# oTFTeatherWing-LT7688.net
KiCad netlist of a schematic drawn in EAGLE
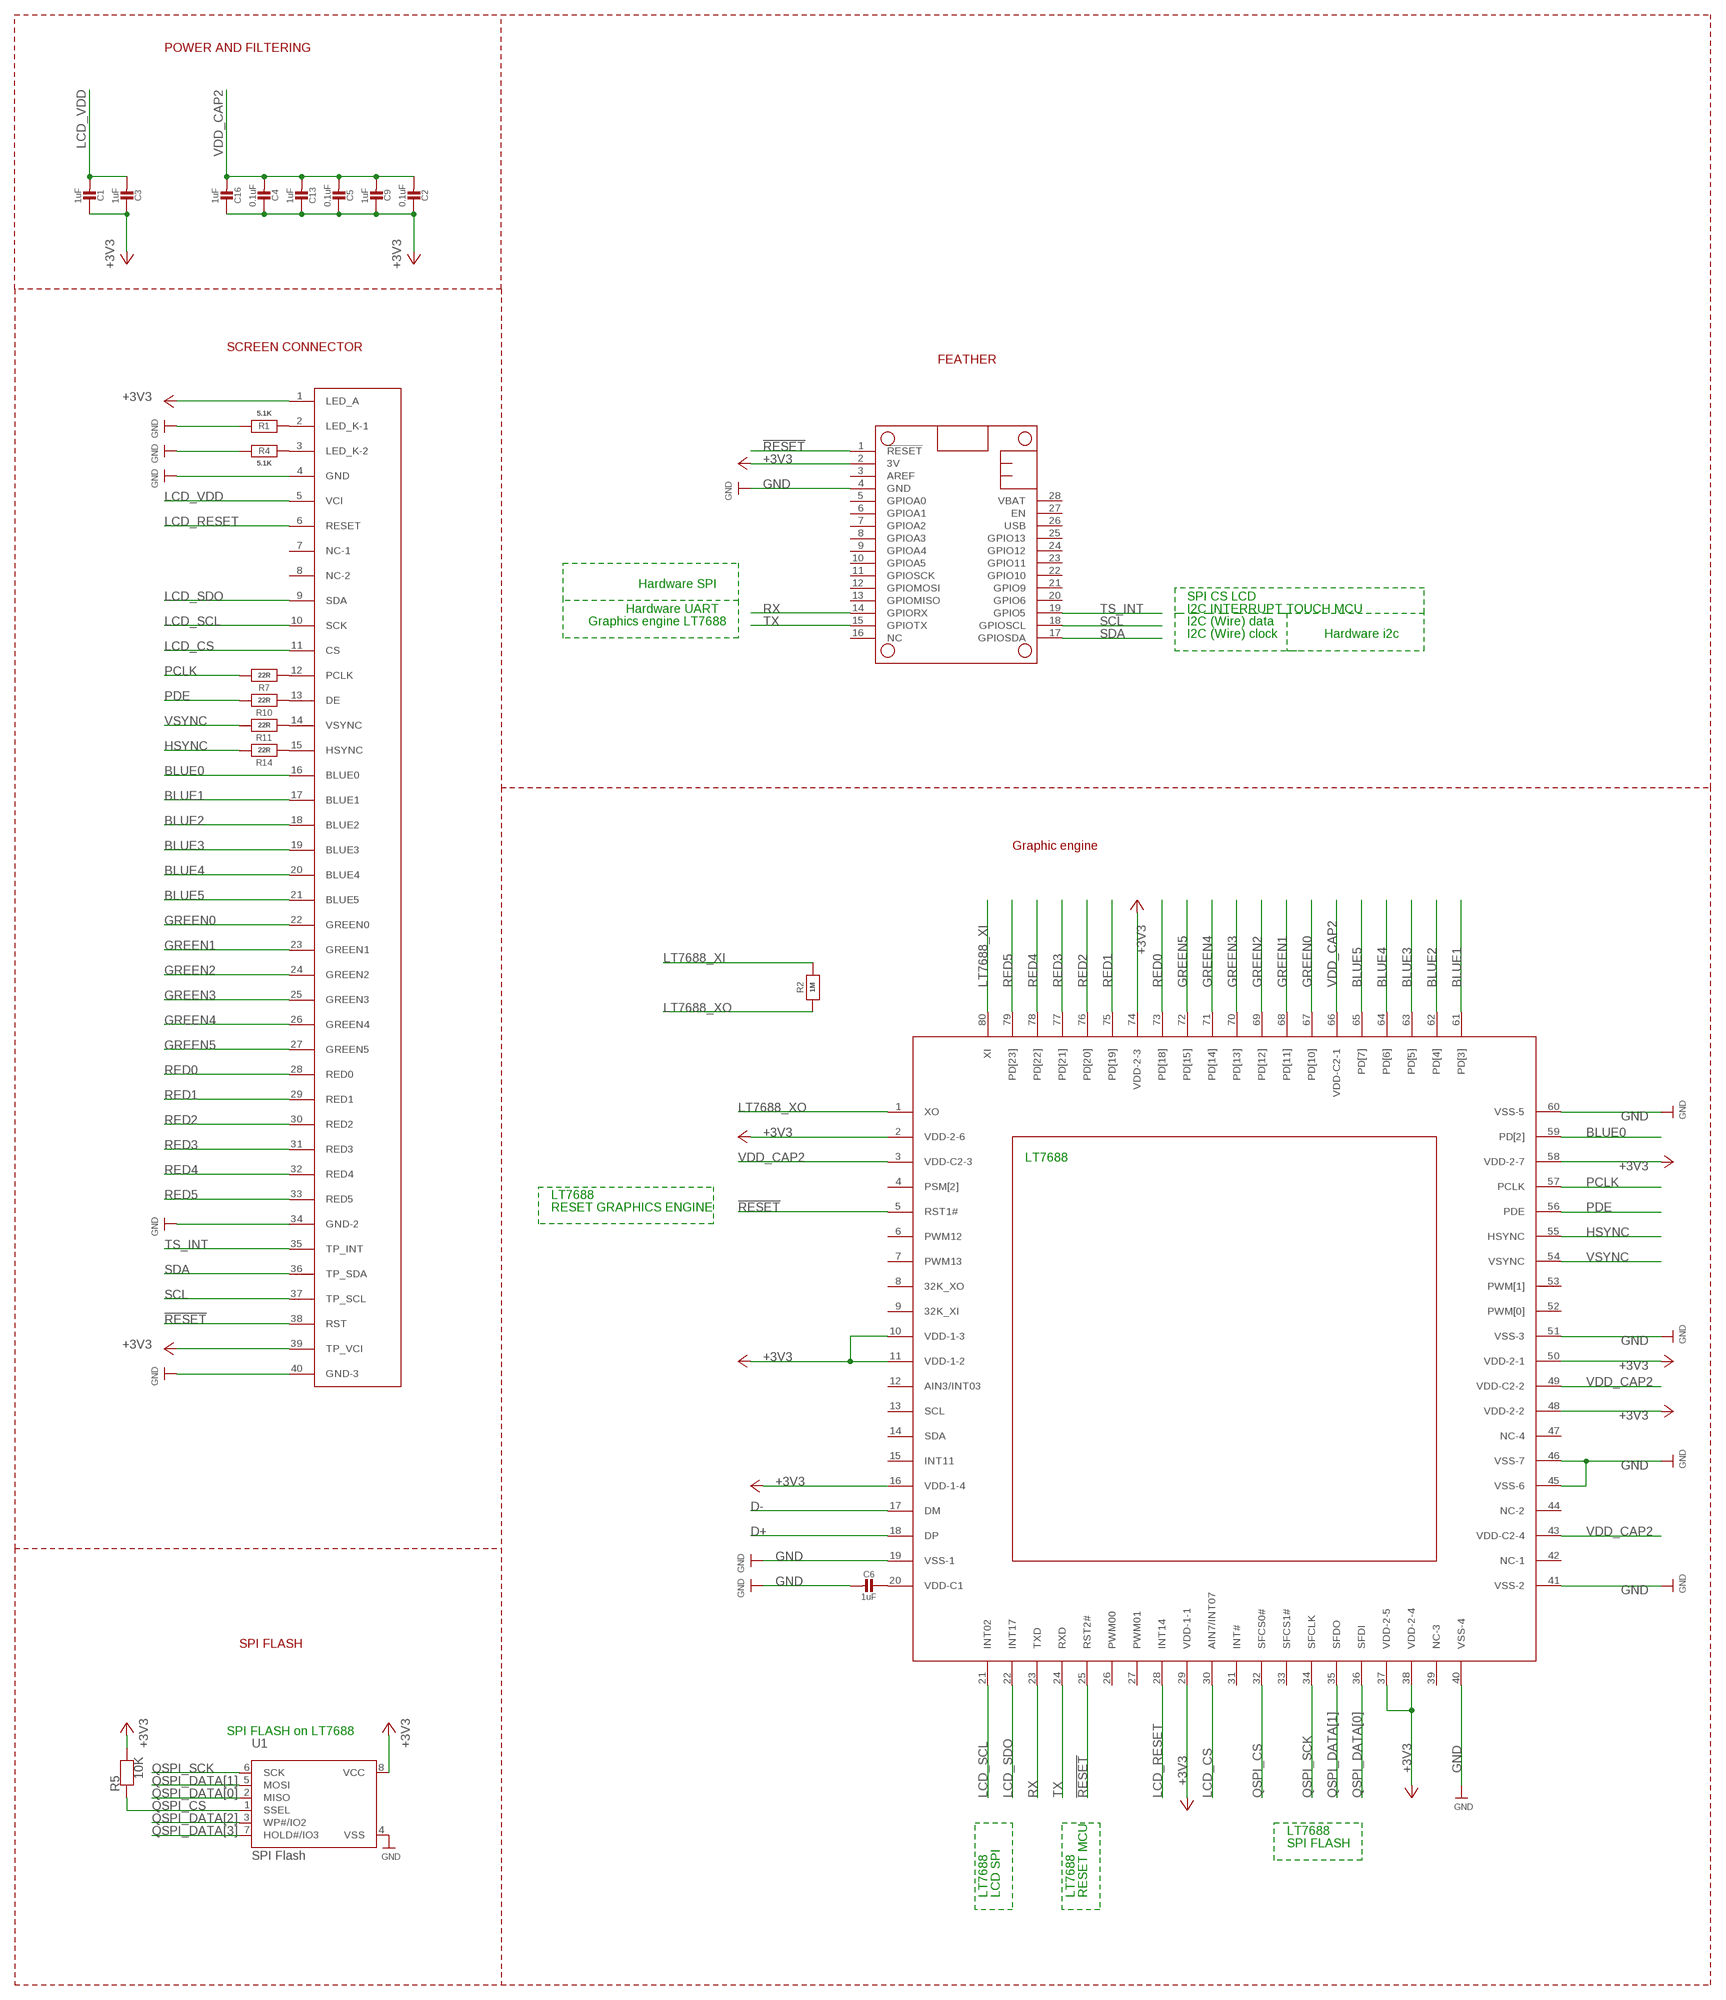
[diagram p0: schematic, sheet 1]

(export (version "E")
  (design (tool "Eeschema 10.0.6"))
  (components
    (comp (ref "C1")
      (value "1uF")
      (footprint "eagle-import:0603-NO")
      (libsource (lib "eagle-import") (part "CAP_CERAMIC0603_NO"))
    )
    (comp (ref "C2")
      (value "0.1uF")
      (footprint "eagle-import:0603-NO")
      (libsource (lib "eagle-import") (part "CAP_CERAMIC0603_NO"))
    )
    (comp (ref "C3")
      (value "1uF")
      (footprint "eagle-import:0603-NO")
      (libsource (lib "eagle-import") (part "CAP_CERAMIC0603_NO"))
    )
    (comp (ref "C4")
      (value "0.1uF")
      (footprint "eagle-import:0603-NO")
      (libsource (lib "eagle-import") (part "CAP_CERAMIC0603_NO"))
    )
    (comp (ref "C5")
      (value "0.1uF")
      (footprint "eagle-import:0603-NO")
      (libsource (lib "eagle-import") (part "CAP_CERAMIC0603_NO"))
    )
    (comp (ref "C6")
      (value "1uF")
      (footprint "eagle-import:0603-NO")
      (libsource (lib "eagle-import") (part "CAP_CERAMIC0603_NO"))
    )
    (comp (ref "C9")
      (value "1uF")
      (footprint "eagle-import:0603-NO")
      (libsource (lib "eagle-import") (part "CAP_CERAMIC0603_NO"))
    )
    (comp (ref "C13")
      (value "1uF")
      (footprint "eagle-import:0603-NO")
      (libsource (lib "eagle-import") (part "CAP_CERAMIC0603_NO"))
    )
    (comp (ref "C16")
      (value "1uF")
      (footprint "eagle-import:0603-NO")
      (libsource (lib "eagle-import") (part "CAP_CERAMIC0603_NO"))
    )
    (comp (ref "MS2")
      (value "FEATHERWING")
      (footprint "eagle-import:FEATHERWING")
      (libsource (lib "eagle-import") (part "FEATHERWING"))
    )
    (comp (ref "R1")
      (value "5.1K")
      (footprint "eagle-import:0603-NO")
      (libsource (lib "eagle-import") (part "RESISTOR_0603_NOOUT"))
    )
    (comp (ref "R2")
      (value "1M")
      (footprint "eagle-import:0603-NO")
      (libsource (lib "eagle-import") (part "RESISTOR_0603_NOOUT"))
    )
    (comp (ref "R4")
      (value "5.1K")
      (footprint "eagle-import:0603-NO")
      (libsource (lib "eagle-import") (part "RESISTOR_0603_NOOUT"))
    )
    (comp (ref "R5")
      (value "10K")
      (footprint "eagle-import:0603-NO")
      (libsource (lib "eagle-import") (part "RESISTOR_0603_NOOUT"))
    )
    (comp (ref "R7")
      (value "22R")
      (footprint "eagle-import:0603-NO")
      (libsource (lib "eagle-import") (part "RESISTOR_0603_NOOUT"))
    )
    (comp (ref "R10")
      (value "22R")
      (footprint "eagle-import:0603-NO")
      (libsource (lib "eagle-import") (part "RESISTOR_0603_NOOUT"))
    )
    (comp (ref "R11")
      (value "22R")
      (footprint "eagle-import:0603-NO")
      (libsource (lib "eagle-import") (part "RESISTOR_0603_NOOUT"))
    )
    (comp (ref "R14")
      (value "22R")
      (footprint "eagle-import:0603-NO")
      (libsource (lib "eagle-import") (part "RESISTOR_0603_NOOUT"))
    )
    (comp (ref "U$1")
      (value "LT7688")
      (footprint "eagle-import:QFN40P900X900X70-81T710N")
      (libsource (lib "eagle-import") (part "LT7688"))
    )
    (comp (ref "U$2")
      (value "FPC-LCD")
      (footprint "eagle-import:XF2M-4015-1F-REVERSE")
      (libsource (lib "eagle-import") (part "FPC-LCD"))
    )
    (comp (ref "U1")
      (value "SPI Flash")
      (footprint "eagle-import:USON8")
      (libsource (lib "eagle-import") (part "SPIFLASH_8PINUX"))
    )
  )
  (nets
    (net (code "1") (name "+3V3") (class "Default")
      (node (ref "C1") (pin "1") (pinfunction "1_1") (pintype "passive"))
      (node (ref "C13") (pin "1") (pinfunction "1_1") (pintype "passive"))
      (node (ref "C16") (pin "1") (pinfunction "1_1") (pintype "passive"))
      (node (ref "C2") (pin "1") (pinfunction "1_1") (pintype "passive"))
      (node (ref "C3") (pin "1") (pinfunction "1_1") (pintype "passive"))
      (node (ref "C4") (pin "1") (pinfunction "1_1") (pintype "passive"))
      (node (ref "C5") (pin "1") (pinfunction "1_1") (pintype "passive"))
      (node (ref "C9") (pin "1") (pinfunction "1_1") (pintype "passive"))
      (node (ref "MS2") (pin "2") (pinfunction "3V_2") (pintype "power_in"))
      (node (ref "R5") (pin "2") (pinfunction "2_2") (pintype "passive"))
      (node (ref "U$1") (pin "10") (pinfunction "VDD-1-3_10") (pintype "bidirectional"))
      (node (ref "U$1") (pin "11") (pinfunction "VDD-1-2_11") (pintype "bidirectional"))
      (node (ref "U$1") (pin "16") (pinfunction "VDD-1-4_16") (pintype "bidirectional"))
      (node (ref "U$1") (pin "2") (pinfunction "VDD-2-6_2") (pintype "bidirectional"))
      (node (ref "U$1") (pin "29") (pinfunction "VDD-1-1_29") (pintype "bidirectional"))
      (node (ref "U$1") (pin "37") (pinfunction "VDD-2-5_37") (pintype "bidirectional"))
      (node (ref "U$1") (pin "38") (pinfunction "VDD-2-4_38") (pintype "bidirectional"))
      (node (ref "U$1") (pin "48") (pinfunction "VDD-2-2_48") (pintype "bidirectional"))
      (node (ref "U$1") (pin "50") (pinfunction "VDD-2-1_50") (pintype "bidirectional"))
      (node (ref "U$1") (pin "58") (pinfunction "VDD-2-7_58") (pintype "bidirectional"))
      (node (ref "U$1") (pin "74") (pinfunction "VDD-2-3_74") (pintype "bidirectional"))
      (node (ref "U$2") (pin "1") (pinfunction "LED_A_1") (pintype "bidirectional"))
      (node (ref "U$2") (pin "39") (pinfunction "TP_VCI_39") (pintype "bidirectional"))
      (node (ref "U1") (pin "8") (pinfunction "VCC_8") (pintype "bidirectional"))
    )
    (net (code "2") (name "/BLUE0") (class "Default")
      (node (ref "U$1") (pin "59") (pinfunction "PD[2]_59") (pintype "bidirectional"))
      (node (ref "U$2") (pin "16") (pinfunction "BLUE0_16") (pintype "bidirectional"))
    )
    (net (code "3") (name "/BLUE1") (class "Default")
      (node (ref "U$1") (pin "61") (pinfunction "PD[3]_61") (pintype "bidirectional"))
      (node (ref "U$2") (pin "17") (pinfunction "BLUE1_17") (pintype "bidirectional"))
    )
    (net (code "4") (name "/BLUE2") (class "Default")
      (node (ref "U$1") (pin "62") (pinfunction "PD[4]_62") (pintype "bidirectional"))
      (node (ref "U$2") (pin "18") (pinfunction "BLUE2_18") (pintype "bidirectional"))
    )
    (net (code "5") (name "/BLUE3") (class "Default")
      (node (ref "U$1") (pin "63") (pinfunction "PD[5]_63") (pintype "bidirectional"))
      (node (ref "U$2") (pin "19") (pinfunction "BLUE3_19") (pintype "bidirectional"))
    )
    (net (code "6") (name "/BLUE4") (class "Default")
      (node (ref "U$1") (pin "64") (pinfunction "PD[6]_64") (pintype "bidirectional"))
      (node (ref "U$2") (pin "20") (pinfunction "BLUE4_20") (pintype "bidirectional"))
    )
    (net (code "7") (name "/BLUE5") (class "Default")
      (node (ref "U$1") (pin "65") (pinfunction "PD[7]_65") (pintype "bidirectional"))
      (node (ref "U$2") (pin "21") (pinfunction "BLUE5_21") (pintype "bidirectional"))
    )
    (net (code "8") (name "/D+") (class "Default")
      (node (ref "U$1") (pin "18") (pinfunction "DP_18") (pintype "bidirectional"))
    )
    (net (code "9") (name "/D-") (class "Default")
      (node (ref "U$1") (pin "17") (pinfunction "DM_17") (pintype "bidirectional"))
    )
    (net (code "10") (name "/GREEN0") (class "Default")
      (node (ref "U$1") (pin "67") (pinfunction "PD[10]_67") (pintype "bidirectional"))
      (node (ref "U$2") (pin "22") (pinfunction "GREEN0_22") (pintype "bidirectional"))
    )
    (net (code "11") (name "/GREEN1") (class "Default")
      (node (ref "U$1") (pin "68") (pinfunction "PD[11]_68") (pintype "bidirectional"))
      (node (ref "U$2") (pin "23") (pinfunction "GREEN1_23") (pintype "bidirectional"))
    )
    (net (code "12") (name "/GREEN2") (class "Default")
      (node (ref "U$1") (pin "69") (pinfunction "PD[12]_69") (pintype "bidirectional"))
      (node (ref "U$2") (pin "24") (pinfunction "GREEN2_24") (pintype "bidirectional"))
    )
    (net (code "13") (name "/GREEN3") (class "Default")
      (node (ref "U$1") (pin "70") (pinfunction "PD[13]_70") (pintype "bidirectional"))
      (node (ref "U$2") (pin "25") (pinfunction "GREEN3_25") (pintype "bidirectional"))
    )
    (net (code "14") (name "/GREEN4") (class "Default")
      (node (ref "U$1") (pin "71") (pinfunction "PD[14]_71") (pintype "bidirectional"))
      (node (ref "U$2") (pin "26") (pinfunction "GREEN4_26") (pintype "bidirectional"))
    )
    (net (code "15") (name "/GREEN5") (class "Default")
      (node (ref "U$1") (pin "72") (pinfunction "PD[15]_72") (pintype "bidirectional"))
      (node (ref "U$2") (pin "27") (pinfunction "GREEN5_27") (pintype "bidirectional"))
    )
    (net (code "16") (name "/HSYNC") (class "Default")
      (node (ref "R14") (pin "2") (pinfunction "2_2") (pintype "passive"))
      (node (ref "U$1") (pin "55") (pinfunction "HSYNC_55") (pintype "bidirectional"))
    )
    (net (code "17") (name "/LCD_CS") (class "Default")
      (node (ref "U$1") (pin "30") (pinfunction "AIN7/INT07_30") (pintype "bidirectional"))
      (node (ref "U$2") (pin "11") (pinfunction "CS_11") (pintype "bidirectional"))
    )
    (net (code "18") (name "/LCD_RESET") (class "Default")
      (node (ref "U$1") (pin "28") (pinfunction "INT14_28") (pintype "bidirectional"))
      (node (ref "U$2") (pin "6") (pinfunction "RESET_6") (pintype "bidirectional"))
    )
    (net (code "19") (name "/LCD_SCL") (class "Default")
      (node (ref "U$1") (pin "21") (pinfunction "INT02_21") (pintype "bidirectional"))
      (node (ref "U$2") (pin "10") (pinfunction "SCK_10") (pintype "bidirectional"))
    )
    (net (code "20") (name "/LCD_SDO") (class "Default")
      (node (ref "U$1") (pin "22") (pinfunction "INT17_22") (pintype "bidirectional"))
      (node (ref "U$2") (pin "9") (pinfunction "SDA_9") (pintype "bidirectional"))
    )
    (net (code "21") (name "/LCD_VDD") (class "Default")
      (node (ref "C1") (pin "2") (pinfunction "2_2") (pintype "passive"))
      (node (ref "C3") (pin "2") (pinfunction "2_2") (pintype "passive"))
      (node (ref "U$2") (pin "5") (pinfunction "VCI_5") (pintype "bidirectional"))
    )
    (net (code "22") (name "/LT7688_XI") (class "Default")
      (node (ref "R2") (pin "2") (pinfunction "2_2") (pintype "passive"))
      (node (ref "U$1") (pin "80") (pinfunction "XI_80") (pintype "bidirectional"))
    )
    (net (code "23") (name "/LT7688_XO") (class "Default")
      (node (ref "R2") (pin "1") (pinfunction "1_1") (pintype "passive"))
      (node (ref "U$1") (pin "1") (pinfunction "XO_1") (pintype "bidirectional"))
    )
    (net (code "24") (name "/PCLK") (class "Default")
      (node (ref "R7") (pin "2") (pinfunction "2_2") (pintype "passive"))
      (node (ref "U$1") (pin "57") (pinfunction "PCLK_57") (pintype "bidirectional"))
    )
    (net (code "25") (name "/PDE") (class "Default")
      (node (ref "R10") (pin "2") (pinfunction "2_2") (pintype "passive"))
      (node (ref "U$1") (pin "56") (pinfunction "PDE_56") (pintype "bidirectional"))
    )
    (net (code "26") (name "/QSPI_CS") (class "Default")
      (node (ref "R5") (pin "1") (pinfunction "1_1") (pintype "passive"))
      (node (ref "U$1") (pin "32") (pinfunction "SFCS0#_32") (pintype "bidirectional"))
      (node (ref "U1") (pin "1") (pinfunction "SSEL_1") (pintype "bidirectional"))
    )
    (net (code "27") (name "/QSPI_DATA[0]") (class "Default")
      (node (ref "U$1") (pin "36") (pinfunction "SFDI_36") (pintype "bidirectional"))
      (node (ref "U1") (pin "2") (pinfunction "MISO_2") (pintype "bidirectional"))
    )
    (net (code "28") (name "/QSPI_DATA[1]") (class "Default")
      (node (ref "U$1") (pin "35") (pinfunction "SFDO_35") (pintype "bidirectional"))
      (node (ref "U1") (pin "5") (pinfunction "MOSI_5") (pintype "bidirectional"))
    )
    (net (code "29") (name "/QSPI_DATA[2]") (class "Default")
      (node (ref "U1") (pin "3") (pinfunction "WP#/IO2_3") (pintype "bidirectional"))
    )
    (net (code "30") (name "/QSPI_DATA[3]") (class "Default")
      (node (ref "U1") (pin "7") (pinfunction "HOLD#/IO3_7") (pintype "bidirectional"))
    )
    (net (code "31") (name "/QSPI_SCK") (class "Default")
      (node (ref "U$1") (pin "34") (pinfunction "SFCLK_34") (pintype "bidirectional"))
      (node (ref "U1") (pin "6") (pinfunction "SCK_6") (pintype "bidirectional"))
    )
    (net (code "32") (name "/RED0") (class "Default")
      (node (ref "U$1") (pin "73") (pinfunction "PD[18]_73") (pintype "bidirectional"))
      (node (ref "U$2") (pin "28") (pinfunction "RED0_28") (pintype "bidirectional"))
    )
    (net (code "33") (name "/RED1") (class "Default")
      (node (ref "U$1") (pin "75") (pinfunction "PD[19]_75") (pintype "bidirectional"))
      (node (ref "U$2") (pin "29") (pinfunction "RED1_29") (pintype "bidirectional"))
    )
    (net (code "34") (name "/RED2") (class "Default")
      (node (ref "U$1") (pin "76") (pinfunction "PD[20]_76") (pintype "bidirectional"))
      (node (ref "U$2") (pin "30") (pinfunction "RED2_30") (pintype "bidirectional"))
    )
    (net (code "35") (name "/RED3") (class "Default")
      (node (ref "U$1") (pin "77") (pinfunction "PD[21]_77") (pintype "bidirectional"))
      (node (ref "U$2") (pin "31") (pinfunction "RED3_31") (pintype "bidirectional"))
    )
    (net (code "36") (name "/RED4") (class "Default")
      (node (ref "U$1") (pin "78") (pinfunction "PD[22]_78") (pintype "bidirectional"))
      (node (ref "U$2") (pin "32") (pinfunction "RED4_32") (pintype "bidirectional"))
    )
    (net (code "37") (name "/RED5") (class "Default")
      (node (ref "U$1") (pin "79") (pinfunction "PD[23]_79") (pintype "bidirectional"))
      (node (ref "U$2") (pin "33") (pinfunction "RED5_33") (pintype "bidirectional"))
    )
    (net (code "38") (name "/RX") (class "Default")
      (node (ref "MS2") (pin "14") (pinfunction "GPIORX_14") (pintype "bidirectional"))
      (node (ref "U$1") (pin "23") (pinfunction "TXD_23") (pintype "bidirectional"))
    )
    (net (code "39") (name "/SCL") (class "Default")
      (node (ref "MS2") (pin "18") (pinfunction "GPIOSCL_18") (pintype "bidirectional"))
      (node (ref "U$2") (pin "37") (pinfunction "TP_SCL_37") (pintype "bidirectional"))
    )
    (net (code "40") (name "/SDA") (class "Default")
      (node (ref "MS2") (pin "17") (pinfunction "GPIOSDA_17") (pintype "bidirectional"))
      (node (ref "U$2") (pin "36") (pinfunction "TP_SDA_36") (pintype "bidirectional"))
    )
    (net (code "41") (name "/TS_INT") (class "Default")
      (node (ref "MS2") (pin "19") (pinfunction "GPIO5_19") (pintype "bidirectional"))
      (node (ref "U$2") (pin "35") (pinfunction "TP_INT_35") (pintype "bidirectional"))
    )
    (net (code "42") (name "/TX") (class "Default")
      (node (ref "MS2") (pin "15") (pinfunction "GPIOTX_15") (pintype "bidirectional"))
      (node (ref "U$1") (pin "24") (pinfunction "RXD_24") (pintype "bidirectional"))
    )
    (net (code "43") (name "/USB") (class "Default")
      (node (ref "MS2") (pin "26") (pinfunction "USB_26") (pintype "power_in"))
    )
    (net (code "44") (name "/VBAT") (class "Default")
      (node (ref "MS2") (pin "28") (pinfunction "VBAT_28") (pintype "power_in"))
    )
    (net (code "45") (name "/VDD_CAP2") (class "Default")
      (node (ref "C13") (pin "2") (pinfunction "2_2") (pintype "passive"))
      (node (ref "C16") (pin "2") (pinfunction "2_2") (pintype "passive"))
      (node (ref "C2") (pin "2") (pinfunction "2_2") (pintype "passive"))
      (node (ref "C4") (pin "2") (pinfunction "2_2") (pintype "passive"))
      (node (ref "C5") (pin "2") (pinfunction "2_2") (pintype "passive"))
      (node (ref "C9") (pin "2") (pinfunction "2_2") (pintype "passive"))
      (node (ref "U$1") (pin "3") (pinfunction "VDD-C2-3_3") (pintype "bidirectional"))
      (node (ref "U$1") (pin "43") (pinfunction "VDD-C2-4_43") (pintype "bidirectional"))
      (node (ref "U$1") (pin "49") (pinfunction "VDD-C2-2_49") (pintype "bidirectional"))
      (node (ref "U$1") (pin "66") (pinfunction "VDD-C2-1_66") (pintype "bidirectional"))
    )
    (net (code "46") (name "/VSYNC") (class "Default")
      (node (ref "R11") (pin "2") (pinfunction "2_2") (pintype "passive"))
      (node (ref "U$1") (pin "54") (pinfunction "VSYNC_54") (pintype "bidirectional"))
    )
    (net (code "47") (name "/~{RESET}") (class "Default")
      (node (ref "MS2") (pin "1") (pinfunction "~{RESET}_1") (pintype "input"))
      (node (ref "U$1") (pin "25") (pinfunction "RST2#_25") (pintype "bidirectional"))
      (node (ref "U$1") (pin "5") (pinfunction "RST1#_5") (pintype "bidirectional"))
      (node (ref "U$2") (pin "38") (pinfunction "RST_38") (pintype "bidirectional"))
    )
    (net (code "48") (name "GND") (class "Default")
      (node (ref "C6") (pin "2") (pinfunction "2_2") (pintype "passive"))
      (node (ref "MS2") (pin "4") (pinfunction "GND_4") (pintype "power_in"))
      (node (ref "R1") (pin "1") (pinfunction "1_1") (pintype "passive"))
      (node (ref "R4") (pin "1") (pinfunction "1_1") (pintype "passive"))
      (node (ref "U$1") (pin "19") (pinfunction "VSS-1_19") (pintype "bidirectional"))
      (node (ref "U$1") (pin "40") (pinfunction "VSS-4_40") (pintype "bidirectional"))
      (node (ref "U$1") (pin "41") (pinfunction "VSS-2_41") (pintype "bidirectional"))
      (node (ref "U$1") (pin "45") (pinfunction "VSS-6_45") (pintype "bidirectional"))
      (node (ref "U$1") (pin "46") (pinfunction "VSS-7_46") (pintype "bidirectional"))
      (node (ref "U$1") (pin "51") (pinfunction "VSS-3_51") (pintype "bidirectional"))
      (node (ref "U$1") (pin "60") (pinfunction "VSS-5_60") (pintype "bidirectional"))
      (node (ref "U$2") (pin "34") (pinfunction "GND-2_34") (pintype "bidirectional"))
      (node (ref "U$2") (pin "4") (pinfunction "GND_4") (pintype "bidirectional"))
      (node (ref "U$2") (pin "40") (pinfunction "GND-3_40") (pintype "bidirectional"))
      (node (ref "U1") (pin "4") (pinfunction "VSS_4") (pintype "bidirectional"))
    )
    (net (code "49") (name "Net-(U$1-VDD-C1)") (class "Default")
      (node (ref "C6") (pin "1") (pinfunction "1_1") (pintype "passive"))
      (node (ref "U$1") (pin "20") (pinfunction "VDD-C1_20") (pintype "bidirectional"))
    )
    (net (code "50") (name "Net-(U$2-DE)") (class "Default")
      (node (ref "R10") (pin "1") (pinfunction "1_1") (pintype "passive"))
      (node (ref "U$2") (pin "13") (pinfunction "DE_13") (pintype "bidirectional"))
    )
    (net (code "51") (name "Net-(U$2-HSYNC)") (class "Default")
      (node (ref "R14") (pin "1") (pinfunction "1_1") (pintype "passive"))
      (node (ref "U$2") (pin "15") (pinfunction "HSYNC_15") (pintype "bidirectional"))
    )
    (net (code "52") (name "Net-(U$2-LED_K-1)") (class "Default")
      (node (ref "R1") (pin "2") (pinfunction "2_2") (pintype "passive"))
      (node (ref "U$2") (pin "2") (pinfunction "LED_K-1_2") (pintype "bidirectional"))
    )
    (net (code "53") (name "Net-(U$2-LED_K-2)") (class "Default")
      (node (ref "R4") (pin "2") (pinfunction "2_2") (pintype "passive"))
      (node (ref "U$2") (pin "3") (pinfunction "LED_K-2_3") (pintype "bidirectional"))
    )
    (net (code "54") (name "Net-(U$2-PCLK)") (class "Default")
      (node (ref "R7") (pin "1") (pinfunction "1_1") (pintype "passive"))
      (node (ref "U$2") (pin "12") (pinfunction "PCLK_12") (pintype "bidirectional"))
    )
    (net (code "55") (name "Net-(U$2-VSYNC)") (class "Default")
      (node (ref "R11") (pin "1") (pinfunction "1_1") (pintype "passive"))
      (node (ref "U$2") (pin "14") (pinfunction "VSYNC_14") (pintype "bidirectional"))
    )
    (net (code "56") (name "unconnected-(MS2-AREF-Pad3)") (class "Default")
      (node (ref "MS2") (pin "3") (pinfunction "AREF_3") (pintype "passive"))
    )
    (net (code "57") (name "unconnected-(MS2-EN-Pad27)") (class "Default")
      (node (ref "MS2") (pin "27") (pinfunction "EN_27") (pintype "passive"))
    )
    (net (code "58") (name "unconnected-(MS2-GPIO6-Pad20)") (class "Default")
      (node (ref "MS2") (pin "20") (pinfunction "GPIO6_20") (pintype "bidirectional"))
    )
    (net (code "59") (name "unconnected-(MS2-GPIO9-Pad21)") (class "Default")
      (node (ref "MS2") (pin "21") (pinfunction "GPIO9_21") (pintype "bidirectional"))
    )
    (net (code "60") (name "unconnected-(MS2-GPIO10-Pad22)") (class "Default")
      (node (ref "MS2") (pin "22") (pinfunction "GPIO10_22") (pintype "bidirectional"))
    )
    (net (code "61") (name "unconnected-(MS2-GPIO11-Pad23)") (class "Default")
      (node (ref "MS2") (pin "23") (pinfunction "GPIO11_23") (pintype "bidirectional"))
    )
    (net (code "62") (name "unconnected-(MS2-GPIO12-Pad24)") (class "Default")
      (node (ref "MS2") (pin "24") (pinfunction "GPIO12_24") (pintype "bidirectional"))
    )
    (net (code "63") (name "unconnected-(MS2-GPIO13-Pad25)") (class "Default")
      (node (ref "MS2") (pin "25") (pinfunction "GPIO13_25") (pintype "bidirectional"))
    )
    (net (code "64") (name "unconnected-(MS2-GPIOA0-Pad5)") (class "Default")
      (node (ref "MS2") (pin "5") (pinfunction "GPIOA0_5") (pintype "bidirectional"))
    )
    (net (code "65") (name "unconnected-(MS2-GPIOA1-Pad6)") (class "Default")
      (node (ref "MS2") (pin "6") (pinfunction "GPIOA1_6") (pintype "bidirectional"))
    )
    (net (code "66") (name "unconnected-(MS2-GPIOA2-Pad7)") (class "Default")
      (node (ref "MS2") (pin "7") (pinfunction "GPIOA2_7") (pintype "bidirectional"))
    )
    (net (code "67") (name "unconnected-(MS2-GPIOA3-Pad8)") (class "Default")
      (node (ref "MS2") (pin "8") (pinfunction "GPIOA3_8") (pintype "bidirectional"))
    )
    (net (code "68") (name "unconnected-(MS2-GPIOA4-Pad9)") (class "Default")
      (node (ref "MS2") (pin "9") (pinfunction "GPIOA4_9") (pintype "bidirectional"))
    )
    (net (code "69") (name "unconnected-(MS2-GPIOA5-Pad10)") (class "Default")
      (node (ref "MS2") (pin "10") (pinfunction "GPIOA5_10") (pintype "bidirectional"))
    )
    (net (code "70") (name "unconnected-(MS2-GPIOMISO-Pad13)") (class "Default")
      (node (ref "MS2") (pin "13") (pinfunction "GPIOMISO_13") (pintype "bidirectional"))
    )
    (net (code "71") (name "unconnected-(MS2-GPIOMOSI-Pad12)") (class "Default")
      (node (ref "MS2") (pin "12") (pinfunction "GPIOMOSI_12") (pintype "bidirectional"))
    )
    (net (code "72") (name "unconnected-(MS2-GPIOSCK-Pad11)") (class "Default")
      (node (ref "MS2") (pin "11") (pinfunction "GPIOSCK_11") (pintype "bidirectional"))
    )
    (net (code "73") (name "unconnected-(MS2-NC-Pad16)") (class "Default")
      (node (ref "MS2") (pin "16") (pinfunction "NC_16") (pintype "passive"))
    )
    (net (code "74") (name "unconnected-(U$1-32K_XI-Pad9)") (class "Default")
      (node (ref "U$1") (pin "9") (pinfunction "32K_XI_9") (pintype "bidirectional"))
    )
    (net (code "75") (name "unconnected-(U$1-32K_XO-Pad8)") (class "Default")
      (node (ref "U$1") (pin "8") (pinfunction "32K_XO_8") (pintype "bidirectional"))
    )
    (net (code "76") (name "unconnected-(U$1-AIN3{slash}INT03-Pad12)") (class "Default")
      (node (ref "U$1") (pin "12") (pinfunction "AIN3/INT03_12") (pintype "bidirectional"))
    )
    (net (code "77") (name "unconnected-(U$1-INT#-Pad31)") (class "Default")
      (node (ref "U$1") (pin "31") (pinfunction "INT#_31") (pintype "bidirectional"))
    )
    (net (code "78") (name "unconnected-(U$1-INT11-Pad15)") (class "Default")
      (node (ref "U$1") (pin "15") (pinfunction "INT11_15") (pintype "bidirectional"))
    )
    (net (code "79") (name "unconnected-(U$1-NC-1-Pad42)") (class "Default")
      (node (ref "U$1") (pin "42") (pinfunction "NC-1_42") (pintype "bidirectional"))
    )
    (net (code "80") (name "unconnected-(U$1-NC-2-Pad44)") (class "Default")
      (node (ref "U$1") (pin "44") (pinfunction "NC-2_44") (pintype "bidirectional"))
    )
    (net (code "81") (name "unconnected-(U$1-NC-3-Pad39)") (class "Default")
      (node (ref "U$1") (pin "39") (pinfunction "NC-3_39") (pintype "bidirectional"))
    )
    (net (code "82") (name "unconnected-(U$1-NC-4-Pad47)") (class "Default")
      (node (ref "U$1") (pin "47") (pinfunction "NC-4_47") (pintype "bidirectional"))
    )
    (net (code "83") (name "unconnected-(U$1-PSM[2]-Pad4)") (class "Default")
      (node (ref "U$1") (pin "4") (pinfunction "PSM[2]_4") (pintype "bidirectional"))
    )
    (net (code "84") (name "unconnected-(U$1-PWM00-Pad26)") (class "Default")
      (node (ref "U$1") (pin "26") (pinfunction "PWM00_26") (pintype "bidirectional"))
    )
    (net (code "85") (name "unconnected-(U$1-PWM01-Pad27)") (class "Default")
      (node (ref "U$1") (pin "27") (pinfunction "PWM01_27") (pintype "bidirectional"))
    )
    (net (code "86") (name "unconnected-(U$1-PWM12-Pad6)") (class "Default")
      (node (ref "U$1") (pin "6") (pinfunction "PWM12_6") (pintype "bidirectional"))
    )
    (net (code "87") (name "unconnected-(U$1-PWM13-Pad7)") (class "Default")
      (node (ref "U$1") (pin "7") (pinfunction "PWM13_7") (pintype "bidirectional"))
    )
    (net (code "88") (name "unconnected-(U$1-PWM[0]-Pad52)") (class "Default")
      (node (ref "U$1") (pin "52") (pinfunction "PWM[0]_52") (pintype "bidirectional"))
    )
    (net (code "89") (name "unconnected-(U$1-PWM[1]-Pad53)") (class "Default")
      (node (ref "U$1") (pin "53") (pinfunction "PWM[1]_53") (pintype "bidirectional"))
    )
    (net (code "90") (name "unconnected-(U$1-SCL-Pad13)") (class "Default")
      (node (ref "U$1") (pin "13") (pinfunction "SCL_13") (pintype "bidirectional"))
    )
    (net (code "91") (name "unconnected-(U$1-SDA-Pad14)") (class "Default")
      (node (ref "U$1") (pin "14") (pinfunction "SDA_14") (pintype "bidirectional"))
    )
    (net (code "92") (name "unconnected-(U$1-SFCS1#-Pad33)") (class "Default")
      (node (ref "U$1") (pin "33") (pinfunction "SFCS1#_33") (pintype "bidirectional"))
    )
    (net (code "93") (name "unconnected-(U$2-NC-1-Pad7)") (class "Default")
      (node (ref "U$2") (pin "7") (pinfunction "NC-1_7") (pintype "bidirectional"))
    )
    (net (code "94") (name "unconnected-(U$2-NC-2-Pad8)") (class "Default")
      (node (ref "U$2") (pin "8") (pinfunction "NC-2_8") (pintype "bidirectional"))
    )
  )
)
